# Analogue_Audio.net
KiCad netlist of a schematic drawn in Altium Designer
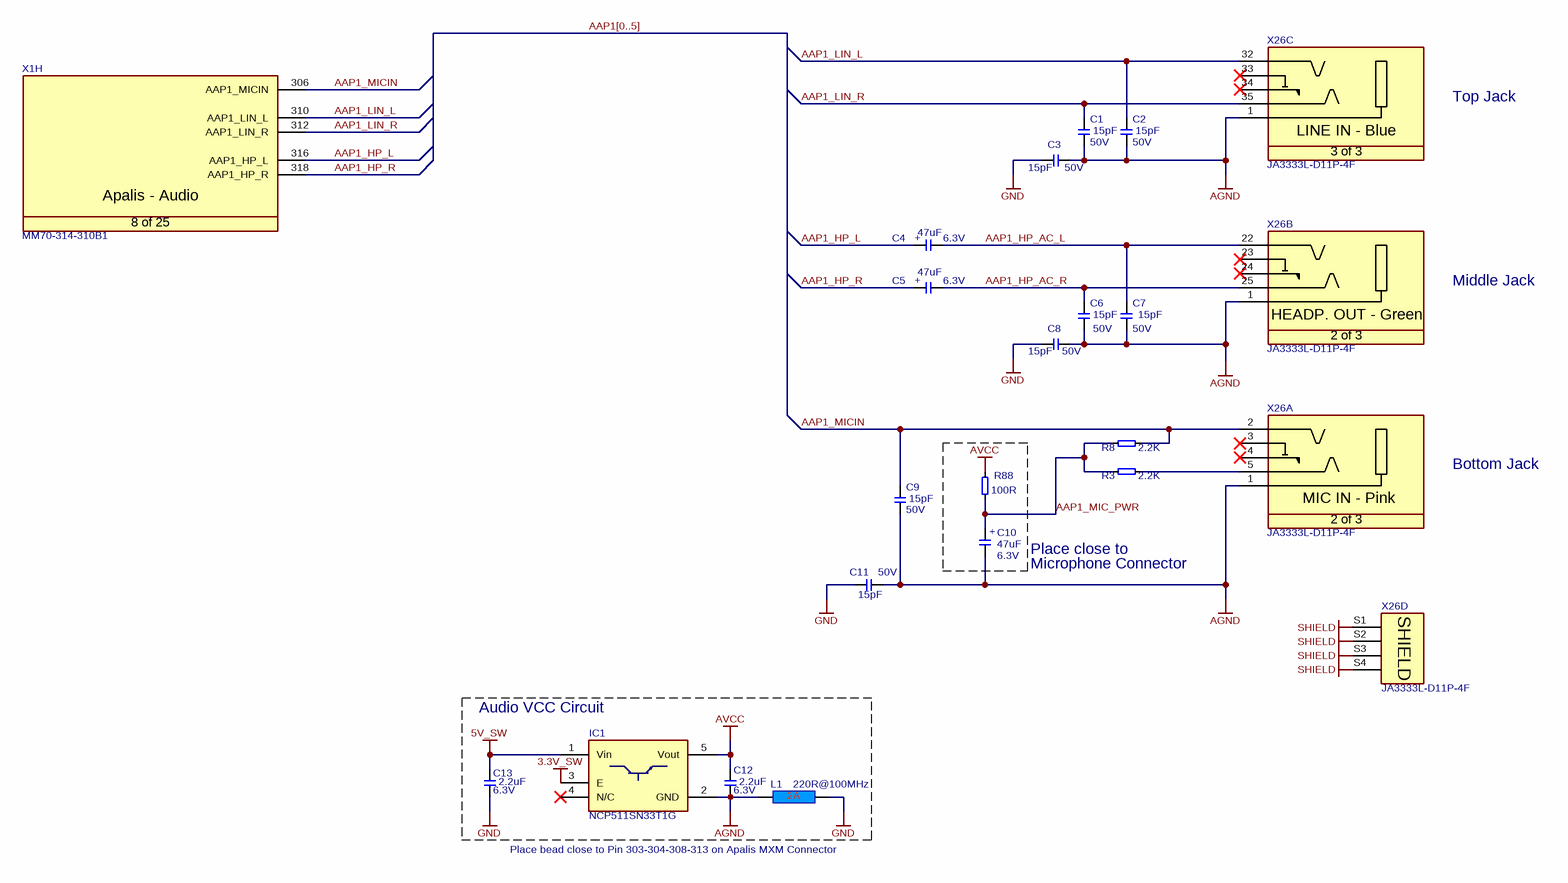
[diagram p0: Analogue_Audio.SchDoc]

(export (version "E")
  (design (tool "Eeschema 10.0.6"))
  (components
    (comp (ref "C1")
      (value "15pF")
      (footprint "T_CAPC0603X33N")
      (description "Capacitor Ceramic NPO 15pF 50V 10% 0603")
      (fields (field (name "TOLERANCE") "10%") (field (name "RATING") "50V"))
      (libsource (lib "Apalis Evaluation Board") (part "C-NPO-15pF-50V-10%-0603"))
    )
    (comp (ref "C2")
      (value "15pF")
      (footprint "T_CAPC0603X33N")
      (description "Capacitor Ceramic NPO 15pF 50V 10% 0603")
      (fields (field (name "TOLERANCE") "10%") (field (name "RATING") "50V"))
      (libsource (lib "Apalis Evaluation Board") (part "C-NPO-15pF-50V-10%-0603"))
    )
    (comp (ref "C3")
      (value "15pF")
      (footprint "T_CAPC0603X33N")
      (description "Capacitor Ceramic NPO 15pF 50V 10% 0603")
      (fields (field (name "TOLERANCE") "10%") (field (name "RATING") "50V"))
      (libsource (lib "Apalis Evaluation Board") (part "C-NPO-15pF-50V-10%-0603"))
    )
    (comp (ref "C4")
      (value "47uF")
      (footprint "T_CAPMP3216X180N")
      (description "Capacitor TA 47uF 6.3V 20% 3216")
      (fields (field (name "TOLERANCE") "20%") (field (name "RATING") "6.3V"))
      (libsource (lib "Apalis Evaluation Board") (part "C-TA-47uF-6.3V-20%-3216"))
    )
    (comp (ref "C5")
      (value "47uF")
      (footprint "T_CAPMP3216X180N")
      (description "Capacitor TA 47uF 6.3V 20% 3216")
      (fields (field (name "TOLERANCE") "20%") (field (name "RATING") "6.3V"))
      (libsource (lib "Apalis Evaluation Board") (part "C-TA-47uF-6.3V-20%-3216"))
    )
    (comp (ref "C6")
      (value "15pF")
      (footprint "T_CAPC0603X33N")
      (description "Capacitor Ceramic NPO 15pF 50V 10% 0603")
      (fields (field (name "TOLERANCE") "10%") (field (name "RATING") "50V"))
      (libsource (lib "Apalis Evaluation Board") (part "C-NPO-15pF-50V-10%-0603"))
    )
    (comp (ref "C7")
      (value "15pF")
      (footprint "T_CAPC0603X33N")
      (description "Capacitor Ceramic NPO 15pF 50V 10% 0603")
      (fields (field (name "TOLERANCE") "10%") (field (name "RATING") "50V"))
      (libsource (lib "Apalis Evaluation Board") (part "C-NPO-15pF-50V-10%-0603"))
    )
    (comp (ref "C8")
      (value "15pF")
      (footprint "T_CAPC0603X33N")
      (description "Capacitor Ceramic NPO 15pF 50V 10% 0603")
      (fields (field (name "TOLERANCE") "10%") (field (name "RATING") "50V"))
      (libsource (lib "Apalis Evaluation Board") (part "C-NPO-15pF-50V-10%-0603"))
    )
    (comp (ref "C9")
      (value "15pF")
      (footprint "T_CAPC0603X33N")
      (description "Capacitor Ceramic NPO 15pF 50V 10% 0603")
      (fields (field (name "TOLERANCE") "10%") (field (name "RATING") "50V"))
      (libsource (lib "Apalis Evaluation Board") (part "C-NPO-15pF-50V-10%-0603"))
    )
    (comp (ref "C10")
      (value "47uF")
      (footprint "T_CAPMP3216X180N")
      (description "Capacitor TA 47uF 6.3V 20% 3216")
      (fields (field (name "TOLERANCE") "20%") (field (name "RATING") "6.3V"))
      (libsource (lib "Apalis Evaluation Board") (part "C-TA-47uF-6.3V-20%-3216"))
    )
    (comp (ref "C11")
      (value "15pF")
      (footprint "T_CAPC0603X33N")
      (description "Capacitor Ceramic NPO 15pF 50V 10% 0603")
      (fields (field (name "TOLERANCE") "10%") (field (name "RATING") "50V"))
      (libsource (lib "Apalis Evaluation Board") (part "C-NPO-15pF-50V-10%-0603"))
    )
    (comp (ref "C12")
      (value "2.2uF")
      (footprint "T_CAPC0603X33N")
      (description "Capacitor Ceramic X5R 2.2uF 6.3V 20% 0603")
      (fields (field (name "TOLERANCE") "20%") (field (name "RATING") "6.3V"))
      (libsource (lib "Apalis Evaluation Board") (part "C-X5R-2.2uF-6.3V-20%-0603"))
    )
    (comp (ref "C13")
      (value "2.2uF")
      (footprint "T_CAPC0603X33N")
      (description "Capacitor Ceramic X5R 2.2uF 6.3V 20% 0603")
      (fields (field (name "TOLERANCE") "20%") (field (name "RATING") "6.3V"))
      (libsource (lib "Apalis Evaluation Board") (part "C-X5R-2.2uF-6.3V-20%-0603"))
    )
    (comp (ref "IC1")
      (value "NCP511SN33T1G")
      (footprint "SOT95P279X142-5N")
      (description "NCP511SN33T1G LDO Regulator")
      (fields (field (name "MANUFACTURER PART NO.") "NCP511SN33T1G"))
      (libsource (lib "Apalis Evaluation Board") (part "IC-ON-NCP511SN33T1G"))
    )
    (comp (ref "L1")
      (value "220R@100MHz")
      (footprint "INDC1608X95N")
      (description "220R@100MHz 2A EMI FILTER")
      (fields (field (name "TOLERANCE") "25%"))
      (libsource (lib "Apalis Evaluation Board") (part "L-220R@100MHz-2A-25%-0603"))
    )
    (comp (ref "R3")
      (value "2.2K")
      (footprint "T_RESC0603X30N")
      (description "Resistor 2.2Kohm 63mW 5% 0603")
      (fields (field (name "TOLERANCE") "5%"))
      (libsource (lib "Apalis Evaluation Board") (part "R-2.2KR-63mW-5%-0603"))
    )
    (comp (ref "R8")
      (value "2.2K")
      (footprint "T_RESC0603X30N")
      (description "Resistor 2.2Kohm 63mW 5% 0603")
      (fields (field (name "TOLERANCE") "5%"))
      (libsource (lib "Apalis Evaluation Board") (part "R-2.2KR-63mW-5%-0603"))
    )
    (comp (ref "R88")
      (value "100R")
      (footprint "T_RESC0603X30N")
      (description "Resistor 100 ohm 63mW 5% 0603")
      (fields (field (name "TOLERANCE") "5%"))
      (libsource (lib "Apalis Evaluation Board") (part "R-100R-63mW-5%-0603"))
    )
    (comp (ref "X1")
      (value "CON-JAE-MM70-314-310B1-314-0.5mm")
      (footprint "T_JAE_MM70-314-310B1")
      (description "MXM3 Connector")
      (fields (field (name "MANUFACTURER PART NO.") "MM70-314-310B1"))
      (libsource (lib "Apalis Evaluation Board") (part "CON-JAE-MM70-314-310B1-314-0.5mm"))
    )
    (comp (ref "X26")
      (value "JA3333L-D11P-4F")
      (footprint "T_FOXCONN_JA3333L-D11P-4F")
      (description "3x Audiojack stereo, 3.5mm with sense")
      (fields (field (name "MANUFACTURER PART NO.") "JA3333L-D11P-4F"))
      (libsource (lib "Apalis Evaluation Board") (part "CON-Foxconn-JA3333L-D11P-4F"))
    )
  )
  (nets
    (net (code "8") (name "/AAP1_HP_AC_L") (class "Default")
      (node (ref "C4") (pin "2") (pinfunction "2_2") (pintype "passive"))
      (node (ref "C7") (pin "2") (pinfunction "2_2") (pintype "passive"))
      (node (ref "X26") (pin "22") (pinfunction "22_22") (pintype "passive"))
    )
    (net (code "9") (name "/AAP1_HP_AC_R") (class "Default")
      (node (ref "C5") (pin "2") (pinfunction "2_2") (pintype "passive"))
      (node (ref "C6") (pin "2") (pinfunction "2_2") (pintype "passive"))
      (node (ref "X26") (pin "25") (pinfunction "25_25") (pintype "passive"))
    )
    (net (code "10") (name "/AAP1_HP_L") (class "Default")
      (node (ref "C4") (pin "1") (pinfunction "1_1") (pintype "passive"))
      (node (ref "X1") (pin "316") (pinfunction "AAP1_HP_L_316") (pintype "passive"))
    )
    (net (code "11") (name "/AAP1_HP_R") (class "Default")
      (node (ref "C5") (pin "1") (pinfunction "1_1") (pintype "passive"))
      (node (ref "X1") (pin "318") (pinfunction "AAP1_HP_R_318") (pintype "passive"))
    )
    (net (code "12") (name "/AAP1_LIN_L") (class "Default")
      (node (ref "C2") (pin "2") (pinfunction "2_2") (pintype "passive"))
      (node (ref "X1") (pin "310") (pinfunction "AAP1_LIN_L_310") (pintype "passive"))
      (node (ref "X26") (pin "32") (pinfunction "32_32") (pintype "passive"))
    )
    (net (code "13") (name "/AAP1_LIN_R") (class "Default")
      (node (ref "C1") (pin "2") (pinfunction "2_2") (pintype "passive"))
      (node (ref "X1") (pin "312") (pinfunction "AAP1_LIN_R_312") (pintype "passive"))
      (node (ref "X26") (pin "35") (pinfunction "35_35") (pintype "passive"))
    )
    (net (code "14") (name "/AAP1_MICIN") (class "Default")
      (node (ref "C9") (pin "2") (pinfunction "2_2") (pintype "passive"))
      (node (ref "R8") (pin "2") (pinfunction "2_2") (pintype "passive"))
      (node (ref "X1") (pin "306") (pinfunction "AAP1_MICIN_306") (pintype "passive"))
      (node (ref "X26") (pin "2") (pinfunction "2_2") (pintype "passive"))
    )
    (net (code "15") (name "/AAP1_MIC_PWR") (class "Default")
      (node (ref "C10") (pin "1") (pinfunction "1_1") (pintype "passive"))
      (node (ref "R3") (pin "1") (pinfunction "1_1") (pintype "passive"))
      (node (ref "R8") (pin "1") (pinfunction "1_1") (pintype "passive"))
      (node (ref "R88") (pin "1") (pinfunction "1_1") (pintype "passive"))
    )
    (net (code "16") (name "3.3V_SW") (class "Default")
      (node (ref "IC1") (pin "3") (pinfunction "E_3") (pintype "passive"))
    )
    (net (code "17") (name "5V_SW") (class "Default")
      (node (ref "C13") (pin "2") (pinfunction "2_2") (pintype "passive"))
      (node (ref "IC1") (pin "1") (pinfunction "Vin_1") (pintype "passive"))
    )
    (net (code "18") (name "AGND") (class "Default")
      (node (ref "C1") (pin "1") (pinfunction "1_1") (pintype "passive"))
      (node (ref "C10") (pin "2") (pinfunction "2_2") (pintype "passive"))
      (node (ref "C11") (pin "1") (pinfunction "1_1") (pintype "passive"))
      (node (ref "C12") (pin "1") (pinfunction "1_1") (pintype "passive"))
      (node (ref "C2") (pin "1") (pinfunction "1_1") (pintype "passive"))
      (node (ref "C3") (pin "2") (pinfunction "2_2") (pintype "passive"))
      (node (ref "C6") (pin "1") (pinfunction "1_1") (pintype "passive"))
      (node (ref "C7") (pin "1") (pinfunction "1_1") (pintype "passive"))
      (node (ref "C8") (pin "2") (pinfunction "2_2") (pintype "passive"))
      (node (ref "C9") (pin "1") (pinfunction "1_1") (pintype "passive"))
      (node (ref "IC1") (pin "2") (pinfunction "GND_2") (pintype "passive"))
      (node (ref "L1") (pin "1") (pinfunction "1_1") (pintype "passive"))
      (node (ref "X26") (pin "1") (pinfunction "1_1") (pintype "passive"))
    )
    (net (code "19") (name "AVCC") (class "Default")
      (node (ref "C12") (pin "2") (pinfunction "2_2") (pintype "passive"))
      (node (ref "IC1") (pin "5") (pinfunction "Vout_5") (pintype "passive"))
      (node (ref "R88") (pin "2") (pinfunction "2_2") (pintype "passive"))
    )
    (net (code "20") (name "GND") (class "Default")
      (node (ref "C11") (pin "2") (pinfunction "2_2") (pintype "passive"))
      (node (ref "C13") (pin "1") (pinfunction "1_1") (pintype "passive"))
      (node (ref "C3") (pin "1") (pinfunction "1_1") (pintype "passive"))
      (node (ref "C8") (pin "1") (pinfunction "1_1") (pintype "passive"))
      (node (ref "L1") (pin "2") (pinfunction "2_2") (pintype "passive"))
    )
    (net (code "21") (name "Net-(R3-Pad2)") (class "Default")
      (node (ref "R3") (pin "2") (pinfunction "2_2") (pintype "passive"))
      (node (ref "X26") (pin "5") (pinfunction "5_5") (pintype "passive"))
    )
    (net (code "22") (name "SHIELD") (class "Default")
      (node (ref "X26") (pin "S1") (pinfunction "SHIELD_S1") (pintype "passive"))
      (node (ref "X26") (pin "S2") (pinfunction "SHIELD_S2") (pintype "passive"))
      (node (ref "X26") (pin "S3") (pinfunction "SHIELD_S3") (pintype "passive"))
      (node (ref "X26") (pin "S4") (pinfunction "SHIELD_S4") (pintype "passive"))
    )
    (net (code "23") (name "unconnected-(IC1-N{slash}C-Pad4)") (class "Default")
      (node (ref "IC1") (pin "4") (pinfunction "N/C_4") (pintype "passive+no_connect"))
    )
    (net (code "24") (name "unconnected-(X26-Pad3)") (class "Default")
      (node (ref "X26") (pin "3") (pinfunction "3_3") (pintype "passive+no_connect"))
    )
    (net (code "25") (name "unconnected-(X26-Pad4)") (class "Default")
      (node (ref "X26") (pin "4") (pinfunction "4_4") (pintype "passive+no_connect"))
    )
    (net (code "26") (name "unconnected-(X26-Pad23)") (class "Default")
      (node (ref "X26") (pin "23") (pinfunction "23_23") (pintype "passive+no_connect"))
    )
    (net (code "27") (name "unconnected-(X26-Pad24)") (class "Default")
      (node (ref "X26") (pin "24") (pinfunction "24_24") (pintype "passive+no_connect"))
    )
    (net (code "28") (name "unconnected-(X26-Pad33)") (class "Default")
      (node (ref "X26") (pin "33") (pinfunction "33_33") (pintype "passive+no_connect"))
    )
    (net (code "29") (name "unconnected-(X26-Pad34)") (class "Default")
      (node (ref "X26") (pin "34") (pinfunction "34_34") (pintype "passive+no_connect"))
    )
  )
)
